# 4082_II.net
KiCad netlist of a schematic drawn in EasyEDA Pro
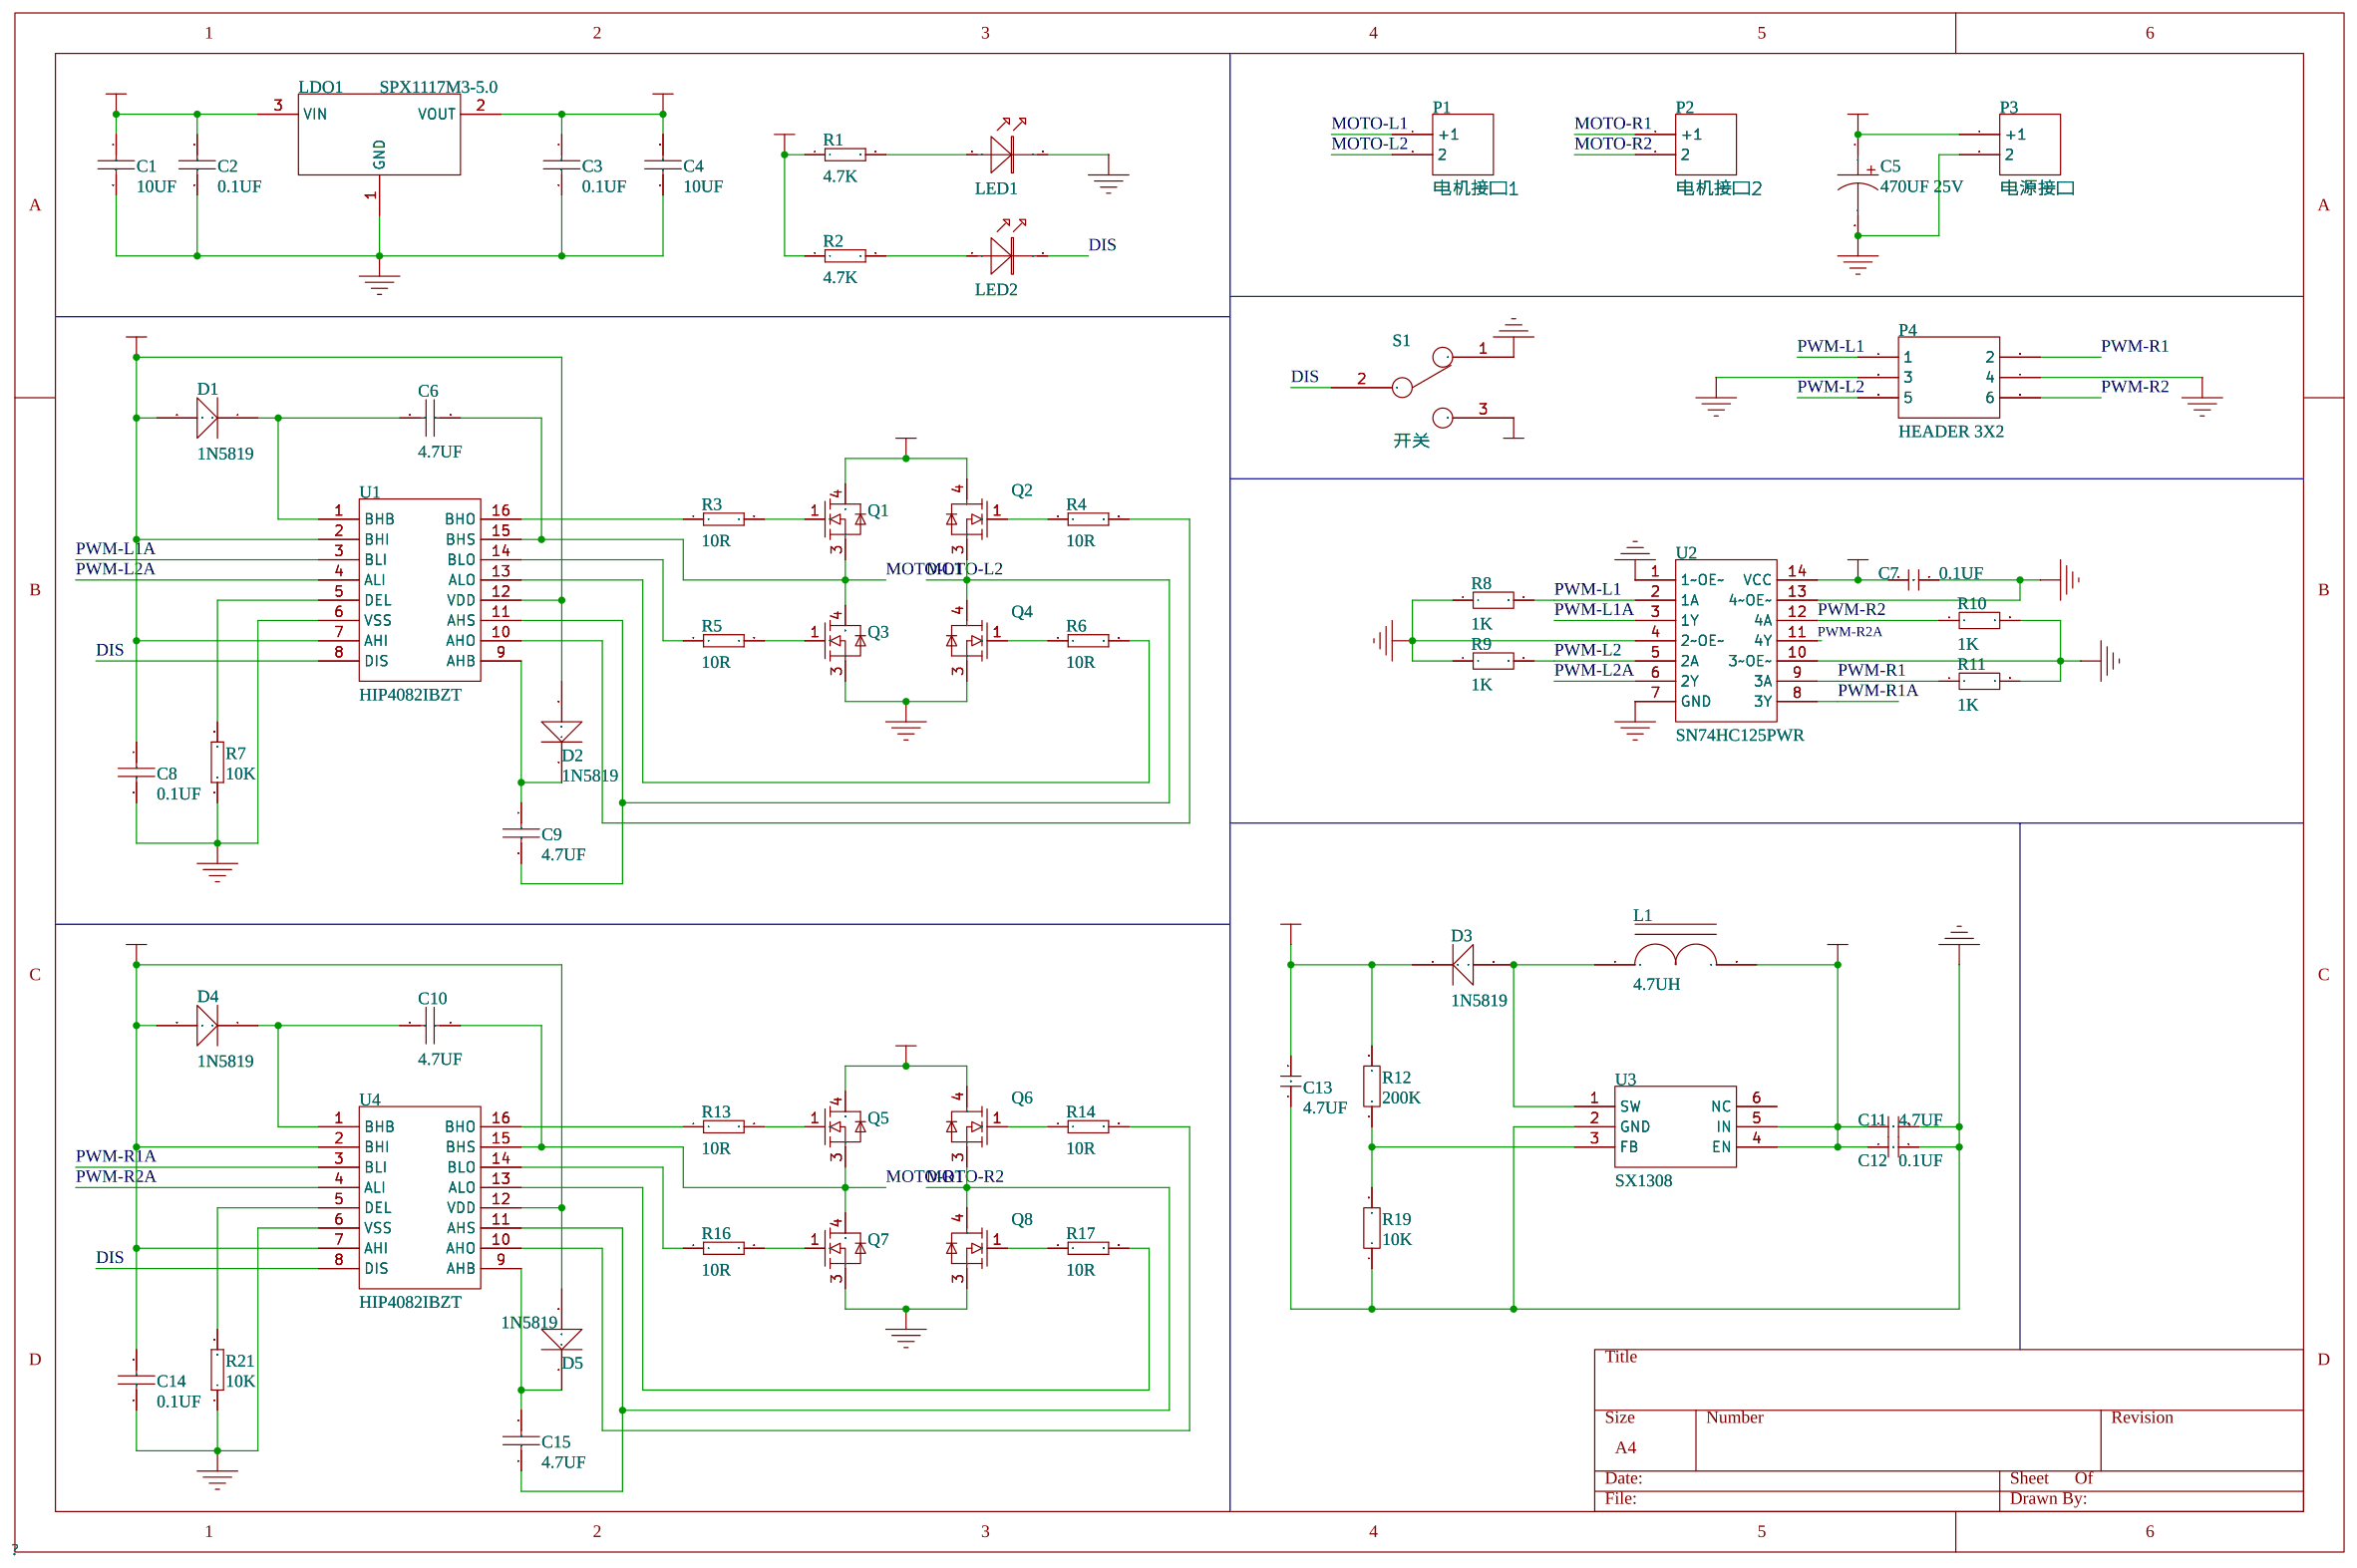
[diagram p0: schematic sheet]

(export (version "E")
  (design (tool "Eeschema 10.0.6"))
  (components
    (comp (ref "C1")
      (value "10UF")
      (footprint "easyedapro:C 0603_L")
      (description "Capacitor")
      (libsource (lib "easyedapro") (part "CAP"))
    )
    (comp (ref "C2")
      (value "0.1UF")
      (footprint "easyedapro:C 0603_L")
      (description "Capacitor")
      (libsource (lib "easyedapro") (part "CAP"))
    )
    (comp (ref "C3")
      (value "0.1UF")
      (footprint "easyedapro:C 0603_L")
      (description "Capacitor")
      (libsource (lib "easyedapro") (part "CAP"))
    )
    (comp (ref "C4")
      (value "10UF")
      (footprint "easyedapro:C 0603_L")
      (description "Capacitor")
      (libsource (lib "easyedapro") (part "CAP"))
    )
    (comp (ref "C5")
      (value "470UF 25V")
      (footprint "easyedapro:CAP-TH_BD10.0-F5.00-D0.6-FD")
      (description "Capacitor")
      (libsource (lib "easyedapro") (part "CAPACITOR POL"))
    )
    (comp (ref "C6")
      (value "4.7UF")
      (footprint "easyedapro:C 0603_L")
      (description "Capacitor")
      (libsource (lib "easyedapro") (part "CAP"))
    )
    (comp (ref "C7")
      (value "0.1UF")
      (footprint "easyedapro:C 0603_L")
      (description "-޼-----Ƭ----")
      (libsource (lib "easyedapro") (part "C"))
    )
    (comp (ref "C8")
      (value "0.1UF")
      (footprint "easyedapro:C 0603_L")
      (description "Capacitor")
      (libsource (lib "easyedapro") (part "CAP"))
    )
    (comp (ref "C9")
      (value "4.7UF")
      (footprint "easyedapro:C 0603_L")
      (description "Capacitor")
      (libsource (lib "easyedapro") (part "CAP"))
    )
    (comp (ref "C10")
      (value "4.7UF")
      (footprint "easyedapro:C 0603_L")
      (description "Capacitor")
      (libsource (lib "easyedapro") (part "CAP"))
    )
    (comp (ref "C11")
      (value "4.7UF")
      (footprint "easyedapro:C 0603_L")
      (description "-޼-----Ƭ----")
      (libsource (lib "easyedapro") (part "C"))
    )
    (comp (ref "C12")
      (value "0.1UF")
      (footprint "easyedapro:C 0603_L")
      (description "-޼-----Ƭ----")
      (libsource (lib "easyedapro") (part "C"))
    )
    (comp (ref "C13")
      (value "4.7UF")
      (footprint "easyedapro:C 0603_L")
      (description "-޼-----Ƭ----")
      (libsource (lib "easyedapro") (part "C"))
    )
    (comp (ref "C14")
      (value "0.1UF")
      (footprint "easyedapro:C 0603_L")
      (description "Capacitor")
      (libsource (lib "easyedapro") (part "CAP"))
    )
    (comp (ref "C15")
      (value "4.7UF")
      (footprint "easyedapro:C 0603_L")
      (description "Capacitor")
      (libsource (lib "easyedapro") (part "CAP"))
    )
    (comp (ref "D1")
      (value "1N5819")
      (footprint "easyedapro:SOD-123_L2.8-W1.8-LS3.7-RD")
      (libsource (lib "easyedapro") (part "1N5819"))
    )
    (comp (ref "D2")
      (value "1N5819")
      (footprint "easyedapro:SOD-123_L2.8-W1.8-LS3.7-RD")
      (libsource (lib "easyedapro") (part "1N5819"))
    )
    (comp (ref "D3")
      (value "1N5819")
      (footprint "easyedapro:SOD-123_L2.8-W1.8-LS3.7-RD")
      (libsource (lib "easyedapro") (part "1N5819"))
    )
    (comp (ref "D4")
      (value "1N5819")
      (footprint "easyedapro:SOD-123_L2.8-W1.8-LS3.7-RD")
      (libsource (lib "easyedapro") (part "1N5819"))
    )
    (comp (ref "D5")
      (value "1N5819")
      (footprint "easyedapro:SOD-123_L2.8-W1.8-LS3.7-RD")
      (libsource (lib "easyedapro") (part "1N5819"))
    )
    (comp (ref "L1")
      (value "4.7UH")
      (footprint "easyedapro:CDRH74")
      (libsource (lib "easyedapro") (part "INDUCTOR 2"))
    )
    (comp (ref "LDO1")
      (value "SPX1117M3-5.0")
      (footprint "easyedapro:PCBComponent_1")
      (libsource (lib "easyedapro") (part "SPX1117M3-5.0"))
    )
    (comp (ref "LED1")
      (value "LED1")
      (footprint "easyedapro:LED0603-R-RD")
      (libsource (lib "easyedapro") (part "LED"))
    )
    (comp (ref "LED2")
      (value "LED2")
      (footprint "easyedapro:LED0603-R-RD")
      (libsource (lib "easyedapro") (part "LED"))
    )
    (comp (ref "P1")
      (value "电机接口1")
      (footprint "easyedapro:CONN-TH_XT30UPB-F")
      (libsource (lib "easyedapro") (part "ӿ"))
    )
    (comp (ref "P2")
      (value "电机接口2")
      (footprint "easyedapro:CONN-TH_XT30UPB-F")
      (libsource (lib "easyedapro") (part "ӿ"))
    )
    (comp (ref "P3")
      (value "电源接口")
      (footprint "easyedapro:CONN-TH_XT30UPB-F")
      (libsource (lib "easyedapro") (part "ӿ"))
    )
    (comp (ref "P4")
      (value "HEADER 3X2")
      (footprint "easyedapro:HDR-TH_6P-P2.54-V-M-R2-C3-S2.54")
      (libsource (lib "easyedapro") (part "HEADER 3X2"))
    )
    (comp (ref "Q1")
      (value "TPH1R403NL")
      (footprint "easyedapro:TO-252-2_L6.5-W6.1-P4.58-LS10.0-BR")
      (libsource (lib "easyedapro") (part "TPH1R403NL_1"))
    )
    (comp (ref "Q2")
      (value "TPH1R403NL")
      (footprint "easyedapro:TO-252-2_L6.5-W6.1-P4.58-LS10.0-BR")
      (libsource (lib "easyedapro") (part "TPH1R403NL"))
    )
    (comp (ref "Q3")
      (value "TPH1R403NL")
      (footprint "easyedapro:TO-252-2_L6.5-W6.1-P4.58-LS10.0-BR")
      (libsource (lib "easyedapro") (part "TPH1R403NL_1"))
    )
    (comp (ref "Q4")
      (value "TPH1R403NL")
      (footprint "easyedapro:TO-252-2_L6.5-W6.1-P4.58-LS10.0-BR")
      (libsource (lib "easyedapro") (part "TPH1R403NL"))
    )
    (comp (ref "Q5")
      (value "TPH1R403NL")
      (footprint "easyedapro:TO-252-2_L6.5-W6.1-P4.58-LS10.0-BR")
      (libsource (lib "easyedapro") (part "TPH1R403NL_1"))
    )
    (comp (ref "Q6")
      (value "TPH1R403NL")
      (footprint "easyedapro:TO-252-2_L6.5-W6.1-P4.58-LS10.0-BR")
      (libsource (lib "easyedapro") (part "TPH1R403NL"))
    )
    (comp (ref "Q7")
      (value "TPH1R403NL")
      (footprint "easyedapro:TO-252-2_L6.5-W6.1-P4.58-LS10.0-BR")
      (libsource (lib "easyedapro") (part "TPH1R403NL_1"))
    )
    (comp (ref "Q8")
      (value "TPH1R403NL")
      (footprint "easyedapro:TO-252-2_L6.5-W6.1-P4.58-LS10.0-BR")
      (libsource (lib "easyedapro") (part "TPH1R403NL"))
    )
    (comp (ref "R1")
      (value "4.7K")
      (footprint "easyedapro:R 0603_L")
      (libsource (lib "easyedapro") (part "RES2"))
    )
    (comp (ref "R2")
      (value "4.7K")
      (footprint "easyedapro:R 0603_L")
      (libsource (lib "easyedapro") (part "RES2"))
    )
    (comp (ref "R3")
      (value "10R")
      (footprint "easyedapro:R 0603_L")
      (libsource (lib "easyedapro") (part "RES2"))
    )
    (comp (ref "R4")
      (value "10R")
      (footprint "easyedapro:R 0603_L")
      (libsource (lib "easyedapro") (part "RES2"))
    )
    (comp (ref "R5")
      (value "10R")
      (footprint "easyedapro:R 0603_L")
      (libsource (lib "easyedapro") (part "RES2"))
    )
    (comp (ref "R6")
      (value "10R")
      (footprint "easyedapro:R 0603_L")
      (libsource (lib "easyedapro") (part "RES2"))
    )
    (comp (ref "R7")
      (value "10K")
      (footprint "easyedapro:R 0603_L")
      (libsource (lib "easyedapro") (part "RES2"))
    )
    (comp (ref "R8")
      (value "1K")
      (footprint "easyedapro:R 0603_L")
      (description "--Ƭ----")
      (libsource (lib "easyedapro") (part "R"))
    )
    (comp (ref "R9")
      (value "1K")
      (footprint "easyedapro:R 0603_L")
      (description "--Ƭ----")
      (libsource (lib "easyedapro") (part "R"))
    )
    (comp (ref "R10")
      (value "1K")
      (footprint "easyedapro:R 0603_L")
      (description "--Ƭ----")
      (libsource (lib "easyedapro") (part "R"))
    )
    (comp (ref "R11")
      (value "1K")
      (footprint "easyedapro:R 0603_L")
      (description "--Ƭ----")
      (libsource (lib "easyedapro") (part "R"))
    )
    (comp (ref "R12")
      (value "200K")
      (footprint "easyedapro:R 0603_L")
      (description "--Ƭ----")
      (libsource (lib "easyedapro") (part "R"))
    )
    (comp (ref "R13")
      (value "10R")
      (footprint "easyedapro:R 0603_L")
      (libsource (lib "easyedapro") (part "RES2"))
    )
    (comp (ref "R14")
      (value "10R")
      (footprint "easyedapro:R 0603_L")
      (libsource (lib "easyedapro") (part "RES2"))
    )
    (comp (ref "R16")
      (value "10R")
      (footprint "easyedapro:R 0603_L")
      (libsource (lib "easyedapro") (part "RES2"))
    )
    (comp (ref "R17")
      (value "10R")
      (footprint "easyedapro:R 0603_L")
      (libsource (lib "easyedapro") (part "RES2"))
    )
    (comp (ref "R19")
      (value "10K")
      (footprint "easyedapro:R 0603_L")
      (description "--Ƭ----")
      (libsource (lib "easyedapro") (part "R"))
    )
    (comp (ref "R21")
      (value "10K")
      (footprint "easyedapro:R 0603_L")
      (libsource (lib "easyedapro") (part "RES2"))
    )
    (comp (ref "S1")
      (value "开关")
      (footprint "easyedapro:SW-TH_SHOU-HAN_SS12D10G4")
      (libsource (lib "easyedapro") (part "autoName_9d6ded750435c7c9"))
    )
    (comp (ref "U1")
      (value "HIP4082IBZT")
      (footprint "easyedapro:SOIC-16_L9.9-W3.9-P1.27-LS6.0-BL")
      (libsource (lib "easyedapro") (part "HIP4082IBZT"))
    )
    (comp (ref "U2")
      (value "SN74HC125PWR")
      (footprint "easyedapro:TSSOP-14_L5.0-W4.4-P0.65-LS6.5-BL")
      (description "--̬-------·------ TSSOP-20")
      (libsource (lib "easyedapro") (part "SN74HC125PWR"))
    )
    (comp (ref "U3")
      (value "SX1308")
      (footprint "easyedapro:SOT-23-6_L2.9-W1.6-P0.95-LS2.8-BR")
      (description "sot-23-6С--ѹDC-DC")
      (libsource (lib "easyedapro") (part "SX1308"))
    )
    (comp (ref "U4")
      (value "HIP4082IBZT")
      (footprint "easyedapro:SOIC-16_L9.9-W3.9-P1.27-LS6.0-BL")
      (libsource (lib "easyedapro") (part "HIP4082IBZT"))
    )
  )
  (nets
    (net (code "1") (name "/DIS") (class "Default")
      (node (ref "LED2") (pin "2") (pinfunction "2_2") (pintype "input"))
      (node (ref "S1") (pin "2") (pinfunction "2_2") (pintype "input"))
      (node (ref "U1") (pin "8") (pinfunction "DIS_8") (pintype "input"))
      (node (ref "U4") (pin "8") (pinfunction "DIS_8") (pintype "input"))
    )
    (net (code "2") (name "/MOTO-L1") (class "Default")
      (node (ref "C6") (pin "2") (pinfunction "2_2") (pintype "input"))
      (node (ref "P1") (pin "1") (pinfunction "+1_1") (pintype "input"))
      (node (ref "Q1") (pin "3") (pinfunction "S_3") (pintype "input"))
      (node (ref "Q3") (pin "4") (pinfunction "D_4") (pintype "input"))
      (node (ref "U1") (pin "15") (pinfunction "BHS_15") (pintype "input"))
    )
    (net (code "3") (name "/MOTO-L2") (class "Default")
      (node (ref "C9") (pin "2") (pinfunction "2_2") (pintype "input"))
      (node (ref "P1") (pin "2") (pinfunction "2_2") (pintype "input"))
      (node (ref "Q2") (pin "3") (pinfunction "S_3") (pintype "input"))
      (node (ref "Q4") (pin "4") (pinfunction "D_4") (pintype "input"))
      (node (ref "U1") (pin "11") (pinfunction "AHS_11") (pintype "input"))
    )
    (net (code "4") (name "/MOTO-R1") (class "Default")
      (node (ref "C10") (pin "2") (pinfunction "2_2") (pintype "input"))
      (node (ref "P2") (pin "1") (pinfunction "+1_1") (pintype "input"))
      (node (ref "Q5") (pin "3") (pinfunction "S_3") (pintype "input"))
      (node (ref "Q7") (pin "4") (pinfunction "D_4") (pintype "input"))
      (node (ref "U4") (pin "15") (pinfunction "BHS_15") (pintype "input"))
    )
    (net (code "5") (name "/MOTO-R2") (class "Default")
      (node (ref "C15") (pin "2") (pinfunction "2_2") (pintype "input"))
      (node (ref "P2") (pin "2") (pinfunction "2_2") (pintype "input"))
      (node (ref "Q6") (pin "3") (pinfunction "S_3") (pintype "input"))
      (node (ref "Q8") (pin "4") (pinfunction "D_4") (pintype "input"))
      (node (ref "U4") (pin "11") (pinfunction "AHS_11") (pintype "input"))
    )
    (net (code "6") (name "/PWM-L1") (class "Default")
      (node (ref "P4") (pin "1") (pinfunction "1_1") (pintype "input"))
      (node (ref "R8") (pin "2") (pinfunction "2_2") (pintype "input"))
      (node (ref "U2") (pin "2") (pinfunction "1A_2") (pintype "input"))
    )
    (net (code "7") (name "/PWM-L1A") (class "Default")
      (node (ref "U1") (pin "3") (pinfunction "BLI_3") (pintype "input"))
      (node (ref "U2") (pin "3") (pinfunction "1Y_3") (pintype "input"))
    )
    (net (code "8") (name "/PWM-L2") (class "Default")
      (node (ref "P4") (pin "5") (pinfunction "5_5") (pintype "input"))
      (node (ref "R9") (pin "2") (pinfunction "2_2") (pintype "input"))
      (node (ref "U2") (pin "5") (pinfunction "2A_5") (pintype "input"))
    )
    (net (code "9") (name "/PWM-L2A") (class "Default")
      (node (ref "U1") (pin "4") (pinfunction "ALI_4") (pintype "input"))
      (node (ref "U2") (pin "6") (pinfunction "2Y_6") (pintype "input"))
    )
    (net (code "10") (name "/PWM-R1") (class "Default")
      (node (ref "P4") (pin "2") (pinfunction "2_2") (pintype "input"))
      (node (ref "R11") (pin "1") (pinfunction "1_1") (pintype "input"))
      (node (ref "U2") (pin "9") (pinfunction "3A_9") (pintype "input"))
    )
    (net (code "11") (name "/PWM-R1A") (class "Default")
      (node (ref "U2") (pin "8") (pinfunction "3Y_8") (pintype "input"))
      (node (ref "U4") (pin "3") (pinfunction "BLI_3") (pintype "input"))
    )
    (net (code "12") (name "/PWM-R2") (class "Default")
      (node (ref "P4") (pin "6") (pinfunction "6_6") (pintype "input"))
      (node (ref "R10") (pin "1") (pinfunction "1_1") (pintype "input"))
      (node (ref "U2") (pin "12") (pinfunction "4A_12") (pintype "input"))
    )
    (net (code "13") (name "/PWM-R2A") (class "Default")
      (node (ref "U2") (pin "11") (pinfunction "4Y_11") (pintype "input"))
      (node (ref "U4") (pin "4") (pinfunction "ALI_4") (pintype "input"))
    )
    (net (code "14") (name "5V") (class "Default")
      (node (ref "C11") (pin "1") (pinfunction "1_1") (pintype "input"))
      (node (ref "C12") (pin "1") (pinfunction "1_1") (pintype "input"))
      (node (ref "C3") (pin "1") (pinfunction "1_1") (pintype "input"))
      (node (ref "C4") (pin "1") (pinfunction "1_1") (pintype "input"))
      (node (ref "C7") (pin "1") (pinfunction "1_1") (pintype "input"))
      (node (ref "L1") (pin "2") (pinfunction "2_2") (pintype "input"))
      (node (ref "LDO1") (pin "2") (pinfunction "VOUT_2") (pintype "input"))
      (node (ref "R1") (pin "1") (pinfunction "1_1") (pintype "input"))
      (node (ref "R2") (pin "1") (pinfunction "1_1") (pintype "input"))
      (node (ref "S1") (pin "3") (pinfunction "3_3") (pintype "input"))
      (node (ref "U2") (pin "14") (pinfunction "VCC_14") (pintype "input"))
      (node (ref "U3") (pin "4") (pinfunction "EN_4") (pintype "input"))
      (node (ref "U3") (pin "5") (pinfunction "IN_5") (pintype "input"))
    )
    (net (code "15") (name "12V") (class "Default")
      (node (ref "C13") (pin "2") (pinfunction "2_2") (pintype "input"))
      (node (ref "C14") (pin "1") (pinfunction "1_1") (pintype "input"))
      (node (ref "C8") (pin "1") (pinfunction "1_1") (pintype "input"))
      (node (ref "D1") (pin "2") (pinfunction "2_2") (pintype "input"))
      (node (ref "D2") (pin "2") (pinfunction "2_2") (pintype "input"))
      (node (ref "D3") (pin "1") (pinfunction "1_1") (pintype "input"))
      (node (ref "D4") (pin "2") (pinfunction "2_2") (pintype "input"))
      (node (ref "D5") (pin "2") (pinfunction "2_2") (pintype "input"))
      (node (ref "R12") (pin "2") (pinfunction "2_2") (pintype "input"))
      (node (ref "U1") (pin "12") (pinfunction "VDD_12") (pintype "input"))
      (node (ref "U1") (pin "2") (pinfunction "BHI_2") (pintype "input"))
      (node (ref "U1") (pin "7") (pinfunction "AHI_7") (pintype "input"))
      (node (ref "U4") (pin "12") (pinfunction "VDD_12") (pintype "input"))
      (node (ref "U4") (pin "2") (pinfunction "BHI_2") (pintype "input"))
      (node (ref "U4") (pin "7") (pinfunction "AHI_7") (pintype "input"))
    )
    (net (code "16") (name "GND") (class "Default")
      (node (ref "C1") (pin "2") (pinfunction "2_2") (pintype "input"))
      (node (ref "C11") (pin "2") (pinfunction "2_2") (pintype "input"))
      (node (ref "C12") (pin "2") (pinfunction "2_2") (pintype "input"))
      (node (ref "C13") (pin "1") (pinfunction "1_1") (pintype "input"))
      (node (ref "C14") (pin "2") (pinfunction "2_2") (pintype "input"))
      (node (ref "C2") (pin "2") (pinfunction "2_2") (pintype "input"))
      (node (ref "C3") (pin "2") (pinfunction "2_2") (pintype "input"))
      (node (ref "C4") (pin "2") (pinfunction "2_2") (pintype "input"))
      (node (ref "C5") (pin "2") (pinfunction "2_2") (pintype "input"))
      (node (ref "C7") (pin "2") (pinfunction "2_2") (pintype "input"))
      (node (ref "C8") (pin "2") (pinfunction "2_2") (pintype "input"))
      (node (ref "LDO1") (pin "1") (pinfunction "GND_1") (pintype "input"))
      (node (ref "LED1") (pin "2") (pinfunction "2_2") (pintype "input"))
      (node (ref "P3") (pin "2") (pinfunction "2_2") (pintype "input"))
      (node (ref "P4") (pin "3") (pinfunction "3_3") (pintype "input"))
      (node (ref "P4") (pin "4") (pinfunction "4_4") (pintype "input"))
      (node (ref "Q3") (pin "3") (pinfunction "S_3") (pintype "input"))
      (node (ref "Q4") (pin "3") (pinfunction "S_3") (pintype "input"))
      (node (ref "Q7") (pin "3") (pinfunction "S_3") (pintype "input"))
      (node (ref "Q8") (pin "3") (pinfunction "S_3") (pintype "input"))
      (node (ref "R10") (pin "2") (pinfunction "2_2") (pintype "input"))
      (node (ref "R11") (pin "2") (pinfunction "2_2") (pintype "input"))
      (node (ref "R19") (pin "1") (pinfunction "1_1") (pintype "input"))
      (node (ref "R21") (pin "1") (pinfunction "1_1") (pintype "input"))
      (node (ref "R7") (pin "1") (pinfunction "1_1") (pintype "input"))
      (node (ref "R8") (pin "1") (pinfunction "1_1") (pintype "input"))
      (node (ref "R9") (pin "1") (pinfunction "1_1") (pintype "input"))
      (node (ref "S1") (pin "1") (pinfunction "1_1") (pintype "input"))
      (node (ref "U1") (pin "6") (pinfunction "VSS_6") (pintype "input"))
      (node (ref "U2") (pin "1") (pinfunction "1~OE~_1") (pintype "input"))
      (node (ref "U2") (pin "10") (pinfunction "3~OE~_10") (pintype "input"))
      (node (ref "U2") (pin "13") (pinfunction "4~OE~_13") (pintype "input"))
      (node (ref "U2") (pin "4") (pinfunction "2~OE~_4") (pintype "input"))
      (node (ref "U2") (pin "7") (pinfunction "GND_7") (pintype "input"))
      (node (ref "U3") (pin "2") (pinfunction "GND_2") (pintype "input"))
      (node (ref "U4") (pin "6") (pinfunction "VSS_6") (pintype "input"))
    )
    (net (code "17") (name "Net-(LED1-Pad1)") (class "Default")
      (node (ref "LED1") (pin "1") (pinfunction "1_1") (pintype "input"))
      (node (ref "R1") (pin "2") (pinfunction "2_2") (pintype "input"))
    )
    (net (code "18") (name "Net-(LED2-Pad1)") (class "Default")
      (node (ref "LED2") (pin "1") (pinfunction "1_1") (pintype "input"))
      (node (ref "R2") (pin "2") (pinfunction "2_2") (pintype "input"))
    )
    (net (code "19") (name "Net-(Q1-G)") (class "Default")
      (node (ref "Q1") (pin "1") (pinfunction "G_1") (pintype "input"))
      (node (ref "R3") (pin "2") (pinfunction "2_2") (pintype "input"))
    )
    (net (code "20") (name "Net-(Q2-G)") (class "Default")
      (node (ref "Q2") (pin "1") (pinfunction "G_1") (pintype "input"))
      (node (ref "R4") (pin "1") (pinfunction "1_1") (pintype "input"))
    )
    (net (code "21") (name "Net-(Q3-G)") (class "Default")
      (node (ref "Q3") (pin "1") (pinfunction "G_1") (pintype "input"))
      (node (ref "R5") (pin "2") (pinfunction "2_2") (pintype "input"))
    )
    (net (code "22") (name "Net-(Q4-G)") (class "Default")
      (node (ref "Q4") (pin "1") (pinfunction "G_1") (pintype "input"))
      (node (ref "R6") (pin "1") (pinfunction "1_1") (pintype "input"))
    )
    (net (code "23") (name "Net-(Q5-G)") (class "Default")
      (node (ref "Q5") (pin "1") (pinfunction "G_1") (pintype "input"))
      (node (ref "R13") (pin "2") (pinfunction "2_2") (pintype "input"))
    )
    (net (code "24") (name "Net-(Q6-G)") (class "Default")
      (node (ref "Q6") (pin "1") (pinfunction "G_1") (pintype "input"))
      (node (ref "R14") (pin "1") (pinfunction "1_1") (pintype "input"))
    )
    (net (code "25") (name "Net-(Q7-G)") (class "Default")
      (node (ref "Q7") (pin "1") (pinfunction "G_1") (pintype "input"))
      (node (ref "R16") (pin "2") (pinfunction "2_2") (pintype "input"))
    )
    (net (code "26") (name "Net-(Q8-G)") (class "Default")
      (node (ref "Q8") (pin "1") (pinfunction "G_1") (pintype "input"))
      (node (ref "R17") (pin "1") (pinfunction "1_1") (pintype "input"))
    )
    (net (code "27") (name "Net-(U1-AHB)") (class "Default")
      (node (ref "C9") (pin "1") (pinfunction "1_1") (pintype "input"))
      (node (ref "D2") (pin "1") (pinfunction "1_1") (pintype "input"))
      (node (ref "U1") (pin "9") (pinfunction "AHB_9") (pintype "input"))
    )
    (net (code "28") (name "Net-(U1-AHO)") (class "Default")
      (node (ref "R4") (pin "2") (pinfunction "2_2") (pintype "input"))
      (node (ref "U1") (pin "10") (pinfunction "AHO_10") (pintype "input"))
    )
    (net (code "29") (name "Net-(U1-ALO)") (class "Default")
      (node (ref "R6") (pin "2") (pinfunction "2_2") (pintype "input"))
      (node (ref "U1") (pin "13") (pinfunction "ALO_13") (pintype "input"))
    )
    (net (code "30") (name "Net-(U1-BHB)") (class "Default")
      (node (ref "C6") (pin "1") (pinfunction "1_1") (pintype "input"))
      (node (ref "D1") (pin "1") (pinfunction "1_1") (pintype "input"))
      (node (ref "U1") (pin "1") (pinfunction "BHB_1") (pintype "input"))
    )
    (net (code "31") (name "Net-(U1-BHO)") (class "Default")
      (node (ref "R3") (pin "1") (pinfunction "1_1") (pintype "input"))
      (node (ref "U1") (pin "16") (pinfunction "BHO_16") (pintype "input"))
    )
    (net (code "32") (name "Net-(U1-BLO)") (class "Default")
      (node (ref "R5") (pin "1") (pinfunction "1_1") (pintype "input"))
      (node (ref "U1") (pin "14") (pinfunction "BLO_14") (pintype "input"))
    )
    (net (code "33") (name "Net-(U1-DEL)") (class "Default")
      (node (ref "R7") (pin "2") (pinfunction "2_2") (pintype "input"))
      (node (ref "U1") (pin "5") (pinfunction "DEL_5") (pintype "input"))
    )
    (net (code "34") (name "Net-(U3-FB)") (class "Default")
      (node (ref "R12") (pin "1") (pinfunction "1_1") (pintype "input"))
      (node (ref "R19") (pin "2") (pinfunction "2_2") (pintype "input"))
      (node (ref "U3") (pin "3") (pinfunction "FB_3") (pintype "input"))
    )
    (net (code "35") (name "Net-(U3-SW)") (class "Default")
      (node (ref "D3") (pin "2") (pinfunction "2_2") (pintype "input"))
      (node (ref "L1") (pin "1") (pinfunction "1_1") (pintype "input"))
      (node (ref "U3") (pin "1") (pinfunction "SW_1") (pintype "input"))
    )
    (net (code "36") (name "Net-(U4-AHB)") (class "Default")
      (node (ref "C15") (pin "1") (pinfunction "1_1") (pintype "input"))
      (node (ref "D5") (pin "1") (pinfunction "1_1") (pintype "input"))
      (node (ref "U4") (pin "9") (pinfunction "AHB_9") (pintype "input"))
    )
    (net (code "37") (name "Net-(U4-AHO)") (class "Default")
      (node (ref "R14") (pin "2") (pinfunction "2_2") (pintype "input"))
      (node (ref "U4") (pin "10") (pinfunction "AHO_10") (pintype "input"))
    )
    (net (code "38") (name "Net-(U4-ALO)") (class "Default")
      (node (ref "R17") (pin "2") (pinfunction "2_2") (pintype "input"))
      (node (ref "U4") (pin "13") (pinfunction "ALO_13") (pintype "input"))
    )
    (net (code "39") (name "Net-(U4-BHB)") (class "Default")
      (node (ref "C10") (pin "1") (pinfunction "1_1") (pintype "input"))
      (node (ref "D4") (pin "1") (pinfunction "1_1") (pintype "input"))
      (node (ref "U4") (pin "1") (pinfunction "BHB_1") (pintype "input"))
    )
    (net (code "40") (name "Net-(U4-BHO)") (class "Default")
      (node (ref "R13") (pin "1") (pinfunction "1_1") (pintype "input"))
      (node (ref "U4") (pin "16") (pinfunction "BHO_16") (pintype "input"))
    )
    (net (code "41") (name "Net-(U4-BLO)") (class "Default")
      (node (ref "R16") (pin "1") (pinfunction "1_1") (pintype "input"))
      (node (ref "U4") (pin "14") (pinfunction "BLO_14") (pintype "input"))
    )
    (net (code "42") (name "Net-(U4-DEL)") (class "Default")
      (node (ref "R21") (pin "2") (pinfunction "2_2") (pintype "input"))
      (node (ref "U4") (pin "5") (pinfunction "DEL_5") (pintype "input"))
    )
    (net (code "43") (name "VCC") (class "Default")
      (node (ref "C1") (pin "1") (pinfunction "1_1") (pintype "input"))
      (node (ref "C2") (pin "1") (pinfunction "1_1") (pintype "input"))
      (node (ref "C5") (pin "1") (pinfunction "1_1") (pintype "input"))
      (node (ref "LDO1") (pin "3") (pinfunction "VIN_3") (pintype "input"))
      (node (ref "P3") (pin "1") (pinfunction "+1_1") (pintype "input"))
      (node (ref "Q1") (pin "4") (pinfunction "D_4") (pintype "input"))
      (node (ref "Q2") (pin "4") (pinfunction "D_4") (pintype "input"))
      (node (ref "Q5") (pin "4") (pinfunction "D_4") (pintype "input"))
      (node (ref "Q6") (pin "4") (pinfunction "D_4") (pintype "input"))
    )
    (net (code "44") (name "unconnected-(U3-NC-Pad6)") (class "Default")
      (node (ref "U3") (pin "6") (pinfunction "NC_6") (pintype "input"))
    )
  )
)
